# mobileduino_2_0.net
KiCad netlist of a schematic drawn in EAGLE
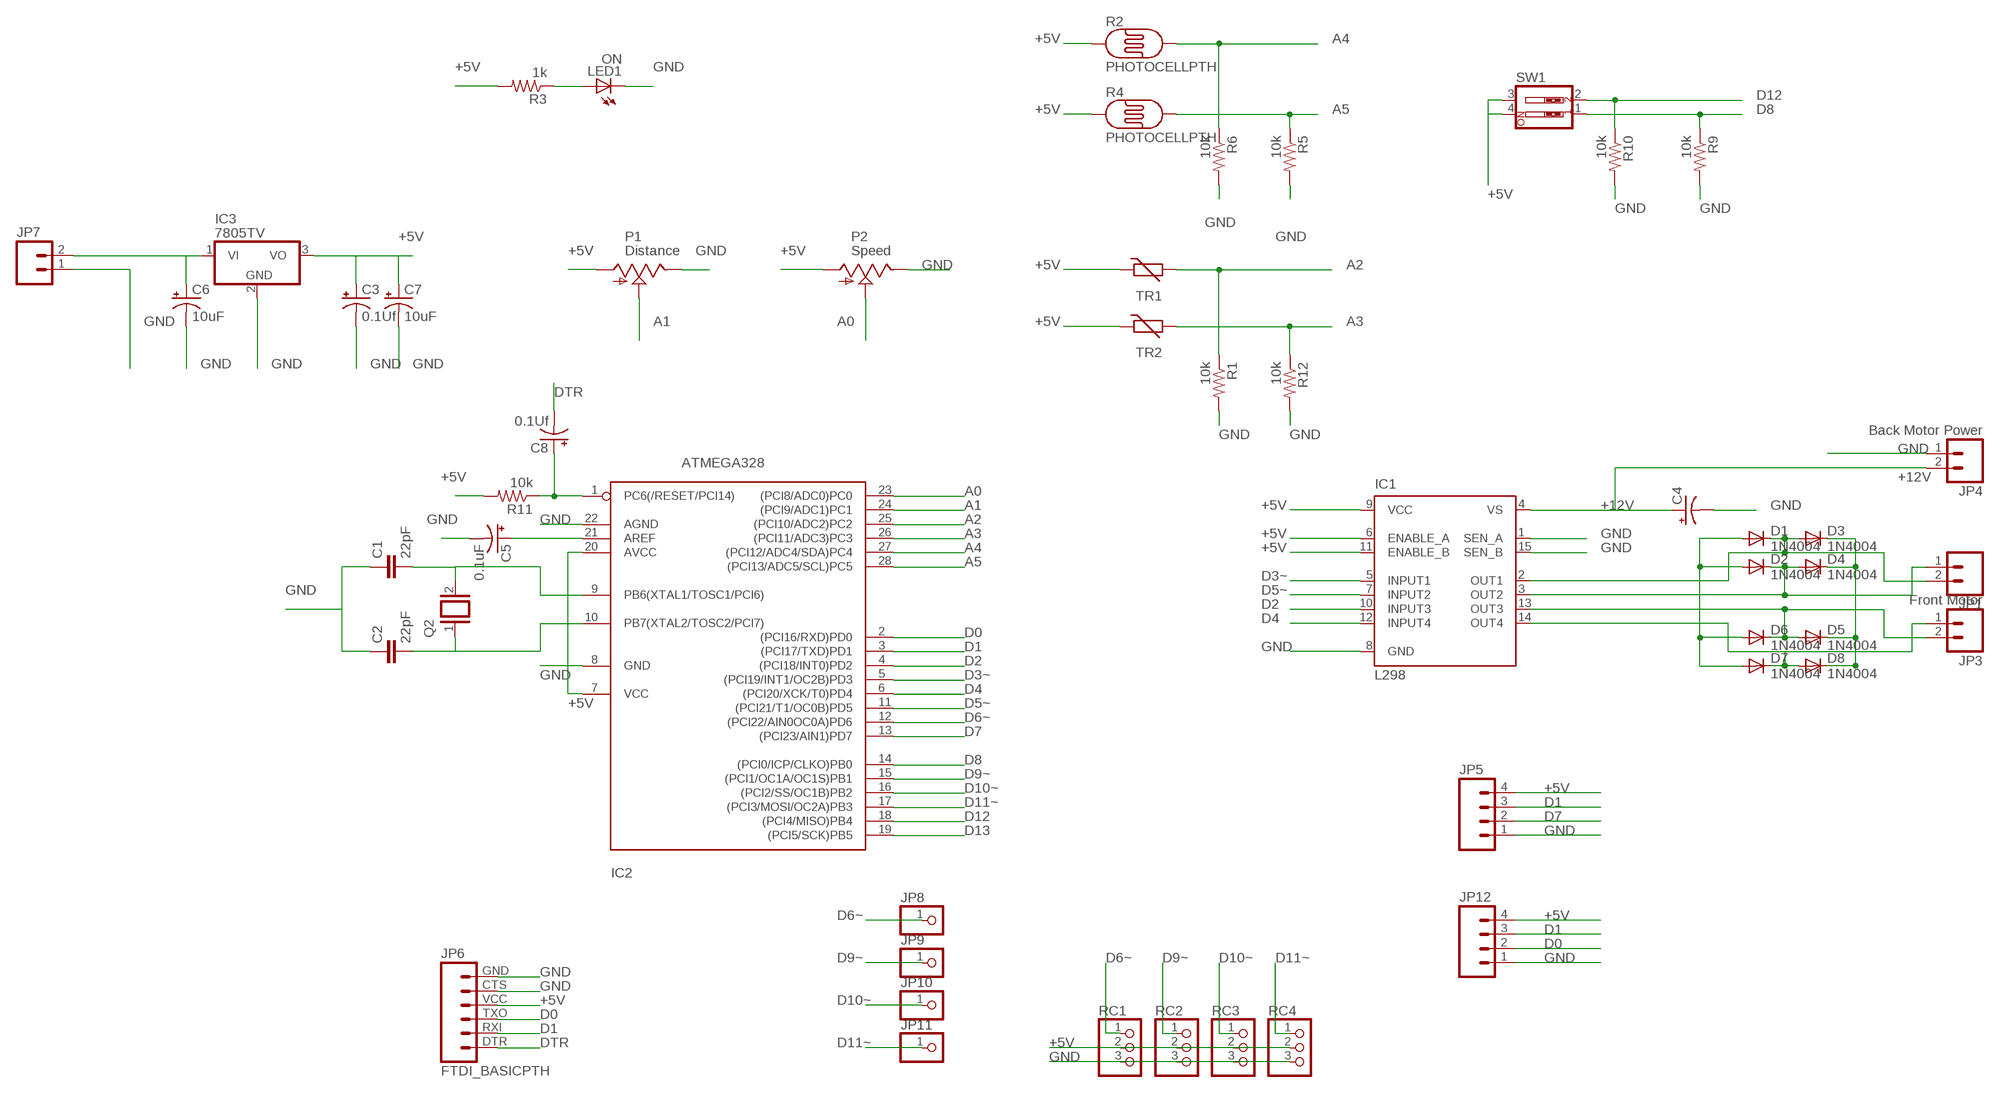
[diagram p0: schematic, sheet 1]

(export (version "E")
  (design (tool "Eeschema 10.0.6"))
  (components
    (comp (ref "C1")
      (value "22pF")
      (footprint "eagle-import:C5B2.5")
      (libsource (lib "eagle-import") (part "C5/2.5"))
    )
    (comp (ref "C2")
      (value "22pF")
      (footprint "eagle-import:C5B2.5")
      (libsource (lib "eagle-import") (part "C5/2.5"))
    )
    (comp (ref "C3")
      (value "0.1Uf")
      (footprint "eagle-import:TT2D5")
      (libsource (lib "eagle-import") (part "CPOL-USTT2D5"))
    )
    (comp (ref "C4")
      (value "CPOL-USTT2D5")
      (footprint "eagle-import:TT2D5")
      (libsource (lib "eagle-import") (part "CPOL-USTT2D5"))
    )
    (comp (ref "C5")
      (value "0.1uF")
      (footprint "eagle-import:TT2D5")
      (libsource (lib "eagle-import") (part "CPOL-USTT2D5"))
    )
    (comp (ref "C6")
      (value "10uF")
      (footprint "eagle-import:TT2D5")
      (libsource (lib "eagle-import") (part "CPOL-USTT2D5"))
    )
    (comp (ref "C7")
      (value "10uF")
      (footprint "eagle-import:TT2D5")
      (libsource (lib "eagle-import") (part "CPOL-USTT2D5"))
    )
    (comp (ref "C8")
      (value "0.1Uf")
      (footprint "eagle-import:TT2D5")
      (libsource (lib "eagle-import") (part "CPOL-USTT2D5"))
    )
    (comp (ref "D1")
      (value "1N4004")
      (footprint "eagle-import:DO41-10")
      (libsource (lib "eagle-import") (part "1N4004"))
    )
    (comp (ref "D2")
      (value "1N4004")
      (footprint "eagle-import:DO41-10")
      (libsource (lib "eagle-import") (part "1N4004"))
    )
    (comp (ref "D3")
      (value "1N4004")
      (footprint "eagle-import:DO41-10")
      (libsource (lib "eagle-import") (part "1N4004"))
    )
    (comp (ref "D4")
      (value "1N4004")
      (footprint "eagle-import:DO41-10")
      (libsource (lib "eagle-import") (part "1N4004"))
    )
    (comp (ref "D5")
      (value "1N4004")
      (footprint "eagle-import:DO41-10")
      (libsource (lib "eagle-import") (part "1N4004"))
    )
    (comp (ref "D6")
      (value "1N4004")
      (footprint "eagle-import:DO41-10")
      (libsource (lib "eagle-import") (part "1N4004"))
    )
    (comp (ref "D7")
      (value "1N4004")
      (footprint "eagle-import:DO41-10")
      (libsource (lib "eagle-import") (part "1N4004"))
    )
    (comp (ref "D8")
      (value "1N4004")
      (footprint "eagle-import:DO41-10")
      (libsource (lib "eagle-import") (part "1N4004"))
    )
    (comp (ref "IC1")
      (value "L298")
      (footprint "eagle-import:MULTIWATT-15")
      (libsource (lib "eagle-import") (part "L298"))
    )
    (comp (ref "IC2")
      (value "ATMEGA328")
      (footprint "eagle-import:DIL28-3")
      (libsource (lib "eagle-import") (part "ATMEGA168PV-10"))
    )
    (comp (ref "IC3")
      (value "7805TV")
      (footprint "eagle-import:TO220V")
      (libsource (lib "eagle-import") (part "78TV05"))
    )
    (comp (ref "JP1")
      (value "M025MM")
      (footprint "eagle-import:SCREWTERMINAL-5MM-2")
      (libsource (lib "eagle-import") (part "M025MM"))
    )
    (comp (ref "JP3")
      (value "Front Motor")
      (footprint "eagle-import:SCREWTERMINAL-5MM-2")
      (libsource (lib "eagle-import") (part "M025MM"))
    )
    (comp (ref "JP4")
      (value "Back Motor Power")
      (footprint "eagle-import:SCREWTERMINAL-5MM-2")
      (libsource (lib "eagle-import") (part "M025MM"))
    )
    (comp (ref "JP5")
      (value "M04PTH")
      (footprint "eagle-import:1X04")
      (libsource (lib "eagle-import") (part "M04PTH"))
    )
    (comp (ref "JP6")
      (value "FTDI_BASICPTH")
      (footprint "eagle-import:FTDI_BASIC")
      (libsource (lib "eagle-import") (part "FTDI_BASICPTH"))
    )
    (comp (ref "JP7")
      (value "M025MM")
      (footprint "eagle-import:SCREWTERMINAL-5MM-2")
      (libsource (lib "eagle-import") (part "M025MM"))
    )
    (comp (ref "JP8")
      (value "PINHD-1X1")
      (footprint "eagle-import:1X01")
      (libsource (lib "eagle-import") (part "PINHD-1X1"))
    )
    (comp (ref "JP9")
      (value "PINHD-1X1")
      (footprint "eagle-import:1X01")
      (libsource (lib "eagle-import") (part "PINHD-1X1"))
    )
    (comp (ref "JP10")
      (value "PINHD-1X1")
      (footprint "eagle-import:1X01")
      (libsource (lib "eagle-import") (part "PINHD-1X1"))
    )
    (comp (ref "JP11")
      (value "PINHD-1X1")
      (footprint "eagle-import:1X01")
      (libsource (lib "eagle-import") (part "PINHD-1X1"))
    )
    (comp (ref "JP12")
      (value "M04PTH")
      (footprint "eagle-import:1X04")
      (libsource (lib "eagle-import") (part "M04PTH"))
    )
    (comp (ref "LED1")
      (value "ON")
      (footprint "eagle-import:LED3MM")
      (libsource (lib "eagle-import") (part "LED3MM"))
    )
    (comp (ref "P1")
      (value "Distance")
      (footprint "eagle-import:CA6V")
      (libsource (lib "eagle-import") (part "TRIM_US-CA6V"))
    )
    (comp (ref "P2")
      (value "Speed")
      (footprint "eagle-import:CA6V")
      (libsource (lib "eagle-import") (part "TRIM_US-CA6V"))
    )
    (comp (ref "Q2")
      (value "XTAL/S")
      (footprint "eagle-import:QS")
      (libsource (lib "eagle-import") (part "XTAL/S"))
    )
    (comp (ref "R1")
      (value "10k")
      (footprint "eagle-import:0204V")
      (libsource (lib "eagle-import") (part "R-US_0204/2V"))
    )
    (comp (ref "R2")
      (value "PHOTOCELLPTH")
      (footprint "eagle-import:PHOTOCELL")
      (libsource (lib "eagle-import") (part "PHOTOCELLPTH"))
    )
    (comp (ref "R3")
      (value "1k")
      (footprint "eagle-import:0204V")
      (libsource (lib "eagle-import") (part "R-US_0204/2V"))
    )
    (comp (ref "R4")
      (value "PHOTOCELLPTH")
      (footprint "eagle-import:PHOTOCELL")
      (libsource (lib "eagle-import") (part "PHOTOCELLPTH"))
    )
    (comp (ref "R5")
      (value "10k")
      (footprint "eagle-import:0204V")
      (libsource (lib "eagle-import") (part "R-US_0204/2V"))
    )
    (comp (ref "R6")
      (value "10k")
      (footprint "eagle-import:0204V")
      (libsource (lib "eagle-import") (part "R-US_0204/2V"))
    )
    (comp (ref "R9")
      (value "10k")
      (footprint "eagle-import:0204V")
      (libsource (lib "eagle-import") (part "R-US_0204/2V"))
    )
    (comp (ref "R10")
      (value "10k")
      (footprint "eagle-import:0204V")
      (libsource (lib "eagle-import") (part "R-US_0204/2V"))
    )
    (comp (ref "R11")
      (value "10k")
      (footprint "eagle-import:0204V")
      (libsource (lib "eagle-import") (part "R-US_0204/2V"))
    )
    (comp (ref "R12")
      (value "10k")
      (footprint "eagle-import:0204V")
      (libsource (lib "eagle-import") (part "R-US_0204/2V"))
    )
    (comp (ref "RC1")
      (value "PINHD-1X3")
      (footprint "eagle-import:1X03")
      (libsource (lib "eagle-import") (part "PINHD-1X3"))
    )
    (comp (ref "RC2")
      (value "PINHD-1X3")
      (footprint "eagle-import:1X03")
      (libsource (lib "eagle-import") (part "PINHD-1X3"))
    )
    (comp (ref "RC3")
      (value "PINHD-1X3")
      (footprint "eagle-import:1X03")
      (libsource (lib "eagle-import") (part "PINHD-1X3"))
    )
    (comp (ref "RC4")
      (value "PINHD-1X3")
      (footprint "eagle-import:1X03")
      (libsource (lib "eagle-import") (part "PINHD-1X3"))
    )
    (comp (ref "SW1")
      (value "SW_DIP-2")
      (footprint "eagle-import:EDG-02")
      (libsource (lib "eagle-import") (part "SW_DIP-2"))
    )
    (comp (ref "TR1")
      (value "THERMISTOR_R-2,5")
      (footprint "eagle-import:RS-2,5")
      (libsource (lib "eagle-import") (part "THERMISTOR_R-2,5"))
    )
    (comp (ref "TR2")
      (value "THERMISTOR_R-2,5")
      (footprint "eagle-import:RS-2,5")
      (libsource (lib "eagle-import") (part "THERMISTOR_R-2,5"))
    )
  )
  (nets
    (net (code "1") (name "/+5V") (class "Default")
      (node (ref "C3") (pin "+") (pinfunction "+_+") (pintype "passive"))
      (node (ref "C7") (pin "+") (pinfunction "+_+") (pintype "passive"))
      (node (ref "IC1") (pin "11") (pinfunction "ENABLE_B_11") (pintype "input"))
      (node (ref "IC1") (pin "6") (pinfunction "ENABLE_A_6") (pintype "input"))
      (node (ref "IC1") (pin "9") (pinfunction "VCC_9") (pintype "power_in"))
      (node (ref "IC2") (pin "20") (pinfunction "AVCC_20") (pintype "bidirectional"))
      (node (ref "IC2") (pin "7") (pinfunction "VCC_7") (pintype "bidirectional"))
      (node (ref "IC3") (pin "3") (pinfunction "VO_3") (pintype "passive"))
      (node (ref "JP12") (pin "4") (pinfunction "4_4") (pintype "passive"))
      (node (ref "JP5") (pin "4") (pinfunction "4_4") (pintype "passive"))
      (node (ref "JP6") (pin "VCC") (pinfunction "4_VCC") (pintype "passive"))
      (node (ref "P1") (pin "A") (pinfunction "A_A") (pintype "passive"))
      (node (ref "P2") (pin "A") (pinfunction "A_A") (pintype "passive"))
      (node (ref "R11") (pin "2") (pinfunction "2_2") (pintype "passive"))
      (node (ref "R2") (pin "1") (pinfunction "P$1_1") (pintype "bidirectional"))
      (node (ref "R3") (pin "2") (pinfunction "2_2") (pintype "passive"))
      (node (ref "R4") (pin "1") (pinfunction "P$1_1") (pintype "bidirectional"))
      (node (ref "RC1") (pin "2") (pinfunction "2_2") (pintype "passive"))
      (node (ref "RC2") (pin "2") (pinfunction "2_2") (pintype "passive"))
      (node (ref "RC3") (pin "2") (pinfunction "2_2") (pintype "passive"))
      (node (ref "RC4") (pin "2") (pinfunction "2_2") (pintype "passive"))
      (node (ref "SW1") (pin "3") (pinfunction "3_3") (pintype "passive"))
      (node (ref "SW1") (pin "4") (pinfunction "4_4") (pintype "passive"))
      (node (ref "TR1") (pin "1") (pinfunction "1_1") (pintype "passive"))
      (node (ref "TR2") (pin "1") (pinfunction "1_1") (pintype "passive"))
    )
    (net (code "2") (name "/+12V") (class "Default")
      (node (ref "C4") (pin "+") (pinfunction "+_+") (pintype "passive"))
      (node (ref "IC1") (pin "4") (pinfunction "VS_4") (pintype "power_in"))
      (node (ref "JP4") (pin "2") (pinfunction "2_2") (pintype "passive"))
    )
    (net (code "3") (name "/A0") (class "Default")
      (node (ref "IC2") (pin "23") (pinfunction "(PCI8/ADC0)PC0_23") (pintype "bidirectional"))
      (node (ref "P2") (pin "S") (pinfunction "S_S") (pintype "passive"))
    )
    (net (code "4") (name "/A1") (class "Default")
      (node (ref "IC2") (pin "24") (pinfunction "(PCI9/ADC1)PC1_24") (pintype "bidirectional"))
      (node (ref "P1") (pin "S") (pinfunction "S_S") (pintype "passive"))
    )
    (net (code "5") (name "/A2") (class "Default")
      (node (ref "IC2") (pin "25") (pinfunction "(PCI10/ADC2)PC2_25") (pintype "bidirectional"))
      (node (ref "R1") (pin "1") (pinfunction "1_1") (pintype "passive"))
      (node (ref "TR1") (pin "2") (pinfunction "2_2") (pintype "passive"))
    )
    (net (code "6") (name "/A3") (class "Default")
      (node (ref "IC2") (pin "26") (pinfunction "(PCI11/ADC3)PC3_26") (pintype "bidirectional"))
      (node (ref "R12") (pin "1") (pinfunction "1_1") (pintype "passive"))
      (node (ref "TR2") (pin "2") (pinfunction "2_2") (pintype "passive"))
    )
    (net (code "7") (name "/A4") (class "Default")
      (node (ref "IC2") (pin "27") (pinfunction "(PCI12/ADC4/SDA)PC4_27") (pintype "bidirectional"))
      (node (ref "R2") (pin "2") (pinfunction "P$2_2") (pintype "bidirectional"))
      (node (ref "R6") (pin "1") (pinfunction "1_1") (pintype "passive"))
    )
    (net (code "8") (name "/A5") (class "Default")
      (node (ref "IC2") (pin "28") (pinfunction "(PCI13/ADC5/SCL)PC5_28") (pintype "bidirectional"))
      (node (ref "R4") (pin "2") (pinfunction "P$2_2") (pintype "bidirectional"))
      (node (ref "R5") (pin "1") (pinfunction "1_1") (pintype "passive"))
    )
    (net (code "9") (name "/D0") (class "Default")
      (node (ref "IC2") (pin "2") (pinfunction "(PCI16/RXD)PD0_2") (pintype "bidirectional"))
      (node (ref "JP12") (pin "2") (pinfunction "2_2") (pintype "passive"))
      (node (ref "JP6") (pin "TXO") (pinfunction "3_TXO") (pintype "passive"))
    )
    (net (code "10") (name "/D1") (class "Default")
      (node (ref "IC2") (pin "3") (pinfunction "(PCI17/TXD)PD1_3") (pintype "bidirectional"))
      (node (ref "JP12") (pin "3") (pinfunction "3_3") (pintype "passive"))
      (node (ref "JP5") (pin "3") (pinfunction "3_3") (pintype "passive"))
      (node (ref "JP6") (pin "RXI") (pinfunction "2_RXI") (pintype "passive"))
    )
    (net (code "11") (name "/D2") (class "Default")
      (node (ref "IC1") (pin "10") (pinfunction "INPUT3_10") (pintype "input"))
      (node (ref "IC2") (pin "4") (pinfunction "(PCI18/INT0)PD2_4") (pintype "bidirectional"))
    )
    (net (code "12") (name "/D3~{}") (class "Default")
      (node (ref "IC1") (pin "5") (pinfunction "INPUT1_5") (pintype "input"))
      (node (ref "IC2") (pin "5") (pinfunction "(PCI19/INT1/OC2B)PD3_5") (pintype "bidirectional"))
    )
    (net (code "13") (name "/D4") (class "Default")
      (node (ref "IC1") (pin "12") (pinfunction "INPUT4_12") (pintype "input"))
      (node (ref "IC2") (pin "6") (pinfunction "(PCI20/XCK/T0)PD4_6") (pintype "bidirectional"))
    )
    (net (code "14") (name "/D5~{}") (class "Default")
      (node (ref "IC1") (pin "7") (pinfunction "INPUT2_7") (pintype "input"))
      (node (ref "IC2") (pin "11") (pinfunction "(PCI21/T1/OC0B)PD5_11") (pintype "bidirectional"))
    )
    (net (code "15") (name "/D6~{}") (class "Default")
      (node (ref "IC2") (pin "12") (pinfunction "(PCI22/AIN0OC0A)PD6_12") (pintype "bidirectional"))
      (node (ref "JP8") (pin "1") (pinfunction "1_1") (pintype "passive"))
      (node (ref "RC1") (pin "1") (pinfunction "1_1") (pintype "passive"))
    )
    (net (code "16") (name "/D7") (class "Default")
      (node (ref "IC2") (pin "13") (pinfunction "(PCI23/AIN1)PD7_13") (pintype "bidirectional"))
      (node (ref "JP5") (pin "2") (pinfunction "2_2") (pintype "passive"))
    )
    (net (code "17") (name "/D8") (class "Default")
      (node (ref "IC2") (pin "14") (pinfunction "(PCI0/ICP/CLKO)PB0_14") (pintype "bidirectional"))
      (node (ref "R9") (pin "1") (pinfunction "1_1") (pintype "passive"))
      (node (ref "SW1") (pin "1") (pinfunction "1_1") (pintype "passive"))
    )
    (net (code "18") (name "/D9~{}") (class "Default")
      (node (ref "IC2") (pin "15") (pinfunction "(PCI1/OC1A/OC1S)PB1_15") (pintype "bidirectional"))
      (node (ref "JP9") (pin "1") (pinfunction "1_1") (pintype "passive"))
      (node (ref "RC2") (pin "1") (pinfunction "1_1") (pintype "passive"))
    )
    (net (code "19") (name "/D10~{}") (class "Default")
      (node (ref "IC2") (pin "16") (pinfunction "(PCI2/SS/OC1B)PB2_16") (pintype "bidirectional"))
      (node (ref "JP10") (pin "1") (pinfunction "1_1") (pintype "passive"))
      (node (ref "RC3") (pin "1") (pinfunction "1_1") (pintype "passive"))
    )
    (net (code "20") (name "/D11~{}") (class "Default")
      (node (ref "IC2") (pin "17") (pinfunction "(PCI3/MOSI/OC2A)PB3_17") (pintype "bidirectional"))
      (node (ref "JP11") (pin "1") (pinfunction "1_1") (pintype "passive"))
      (node (ref "RC4") (pin "1") (pinfunction "1_1") (pintype "passive"))
    )
    (net (code "21") (name "/D12") (class "Default")
      (node (ref "IC2") (pin "18") (pinfunction "(PCI4/MISO)PB4_18") (pintype "bidirectional"))
      (node (ref "R10") (pin "1") (pinfunction "1_1") (pintype "passive"))
      (node (ref "SW1") (pin "2") (pinfunction "2_2") (pintype "passive"))
    )
    (net (code "22") (name "/D13") (class "Default")
      (node (ref "IC2") (pin "19") (pinfunction "(PCI5/SCK)PB5_19") (pintype "bidirectional"))
    )
    (net (code "23") (name "/DTR") (class "Default")
      (node (ref "C8") (pin "-") (pinfunction "-_-") (pintype "passive"))
      (node (ref "JP6") (pin "DTR") (pinfunction "1_DTR") (pintype "passive"))
    )
    (net (code "24") (name "/GND") (class "Default")
      (node (ref "C1") (pin "1") (pinfunction "1_1") (pintype "passive"))
      (node (ref "C2") (pin "1") (pinfunction "1_1") (pintype "passive"))
      (node (ref "C3") (pin "-") (pinfunction "-_-") (pintype "passive"))
      (node (ref "C4") (pin "-") (pinfunction "-_-") (pintype "passive"))
      (node (ref "C5") (pin "-") (pinfunction "-_-") (pintype "passive"))
      (node (ref "C6") (pin "-") (pinfunction "-_-") (pintype "passive"))
      (node (ref "C7") (pin "-") (pinfunction "-_-") (pintype "passive"))
      (node (ref "IC1") (pin "1") (pinfunction "SEN_A_1") (pintype "input"))
      (node (ref "IC1") (pin "15") (pinfunction "SEN_B_15") (pintype "input"))
      (node (ref "IC1") (pin "8") (pinfunction "GND_8") (pintype "power_in"))
      (node (ref "IC2") (pin "22") (pinfunction "AGND_22") (pintype "bidirectional"))
      (node (ref "IC2") (pin "8") (pinfunction "GND_8") (pintype "bidirectional"))
      (node (ref "IC3") (pin "2") (pinfunction "GND_2") (pintype "passive"))
      (node (ref "JP12") (pin "1") (pinfunction "1_1") (pintype "passive"))
      (node (ref "JP4") (pin "1") (pinfunction "1_1") (pintype "passive"))
      (node (ref "JP5") (pin "1") (pinfunction "1_1") (pintype "passive"))
      (node (ref "JP6") (pin "CTS") (pinfunction "5_CTS") (pintype "passive"))
      (node (ref "JP6") (pin "GND") (pinfunction "6_GND") (pintype "passive"))
      (node (ref "JP7") (pin "1") (pinfunction "1_1") (pintype "passive"))
      (node (ref "LED1") (pin "K") (pinfunction "C_K") (pintype "passive"))
      (node (ref "P1") (pin "E") (pinfunction "E_E") (pintype "passive"))
      (node (ref "P2") (pin "E") (pinfunction "E_E") (pintype "passive"))
      (node (ref "R1") (pin "2") (pinfunction "2_2") (pintype "passive"))
      (node (ref "R10") (pin "2") (pinfunction "2_2") (pintype "passive"))
      (node (ref "R12") (pin "2") (pinfunction "2_2") (pintype "passive"))
      (node (ref "R5") (pin "2") (pinfunction "2_2") (pintype "passive"))
      (node (ref "R6") (pin "2") (pinfunction "2_2") (pintype "passive"))
      (node (ref "R9") (pin "2") (pinfunction "2_2") (pintype "passive"))
      (node (ref "RC1") (pin "3") (pinfunction "3_3") (pintype "passive"))
      (node (ref "RC2") (pin "3") (pinfunction "3_3") (pintype "passive"))
      (node (ref "RC3") (pin "3") (pinfunction "3_3") (pintype "passive"))
      (node (ref "RC4") (pin "3") (pinfunction "3_3") (pintype "passive"))
    )
    (net (code "25") (name "Net-(D1-PadA)") (class "Default")
      (node (ref "D1") (pin "A") (pinfunction "A_A") (pintype "passive"))
      (node (ref "D2") (pin "A") (pinfunction "A_A") (pintype "passive"))
      (node (ref "D6") (pin "A") (pinfunction "A_A") (pintype "passive"))
      (node (ref "D7") (pin "A") (pinfunction "A_A") (pintype "passive"))
    )
    (net (code "26") (name "Net-(D3-PadC)") (class "Default")
      (node (ref "D3") (pin "C") (pinfunction "C_C") (pintype "passive"))
      (node (ref "D4") (pin "C") (pinfunction "C_C") (pintype "passive"))
      (node (ref "D5") (pin "C") (pinfunction "C_C") (pintype "passive"))
      (node (ref "D8") (pin "C") (pinfunction "C_C") (pintype "passive"))
    )
    (net (code "27") (name "Net-(IC1-OUT1)") (class "Default")
      (node (ref "D1") (pin "C") (pinfunction "C_C") (pintype "passive"))
      (node (ref "D3") (pin "A") (pinfunction "A_A") (pintype "passive"))
      (node (ref "IC1") (pin "2") (pinfunction "OUT1_2") (pintype "output"))
      (node (ref "JP1") (pin "2") (pinfunction "2_2") (pintype "passive"))
    )
    (net (code "28") (name "Net-(IC1-OUT2)") (class "Default")
      (node (ref "D2") (pin "C") (pinfunction "C_C") (pintype "passive"))
      (node (ref "D4") (pin "A") (pinfunction "A_A") (pintype "passive"))
      (node (ref "IC1") (pin "3") (pinfunction "OUT2_3") (pintype "output"))
      (node (ref "JP1") (pin "1") (pinfunction "1_1") (pintype "passive"))
    )
    (net (code "29") (name "Net-(IC1-OUT3)") (class "Default")
      (node (ref "D5") (pin "A") (pinfunction "A_A") (pintype "passive"))
      (node (ref "D6") (pin "C") (pinfunction "C_C") (pintype "passive"))
      (node (ref "IC1") (pin "13") (pinfunction "OUT3_13") (pintype "output"))
      (node (ref "JP3") (pin "2") (pinfunction "2_2") (pintype "passive"))
    )
    (net (code "30") (name "Net-(IC1-OUT4)") (class "Default")
      (node (ref "D7") (pin "C") (pinfunction "C_C") (pintype "passive"))
      (node (ref "D8") (pin "A") (pinfunction "A_A") (pintype "passive"))
      (node (ref "IC1") (pin "14") (pinfunction "OUT4_14") (pintype "output"))
      (node (ref "JP3") (pin "1") (pinfunction "1_1") (pintype "passive"))
    )
    (net (code "31") (name "Net-(IC2-AREF)") (class "Default")
      (node (ref "C5") (pin "+") (pinfunction "+_+") (pintype "passive"))
      (node (ref "IC2") (pin "21") (pinfunction "AREF_21") (pintype "bidirectional"))
    )
    (net (code "32") (name "Net-(IC2-PB6(XTAL1{slash}TOSC1{slash}PCI6))") (class "Default")
      (node (ref "C1") (pin "2") (pinfunction "2_2") (pintype "passive"))
      (node (ref "IC2") (pin "9") (pinfunction "PB6(XTAL1/TOSC1/PCI6)_9") (pintype "bidirectional"))
      (node (ref "Q2") (pin "2") (pinfunction "2_2") (pintype "passive"))
    )
    (net (code "33") (name "Net-(IC2-PB7(XTAL2{slash}TOSC2{slash}PCI7))") (class "Default")
      (node (ref "C2") (pin "2") (pinfunction "2_2") (pintype "passive"))
      (node (ref "IC2") (pin "10") (pinfunction "PB7(XTAL2/TOSC2/PCI7)_10") (pintype "bidirectional"))
      (node (ref "Q2") (pin "1") (pinfunction "1_1") (pintype "passive"))
    )
    (net (code "34") (name "Net-(IC2-PC6({slash}RESET{slash}PCI14))") (class "Default")
      (node (ref "C8") (pin "+") (pinfunction "+_+") (pintype "passive"))
      (node (ref "IC2") (pin "1") (pinfunction "PC6(/RESET/PCI14)_1") (pintype "bidirectional"))
      (node (ref "R11") (pin "1") (pinfunction "1_1") (pintype "passive"))
    )
    (net (code "35") (name "Net-(IC3-VI)") (class "Default")
      (node (ref "C6") (pin "+") (pinfunction "+_+") (pintype "passive"))
      (node (ref "IC3") (pin "1") (pinfunction "VI_1") (pintype "input"))
      (node (ref "JP7") (pin "2") (pinfunction "2_2") (pintype "passive"))
    )
    (net (code "36") (name "Net-(LED1-PadA)") (class "Default")
      (node (ref "LED1") (pin "A") (pinfunction "A_A") (pintype "passive"))
      (node (ref "R3") (pin "1") (pinfunction "1_1") (pintype "passive"))
    )
  )
)
